# 3_3VBuck_MP2236_P1.net
KiCad netlist of a schematic drawn in EasyEDA Pro
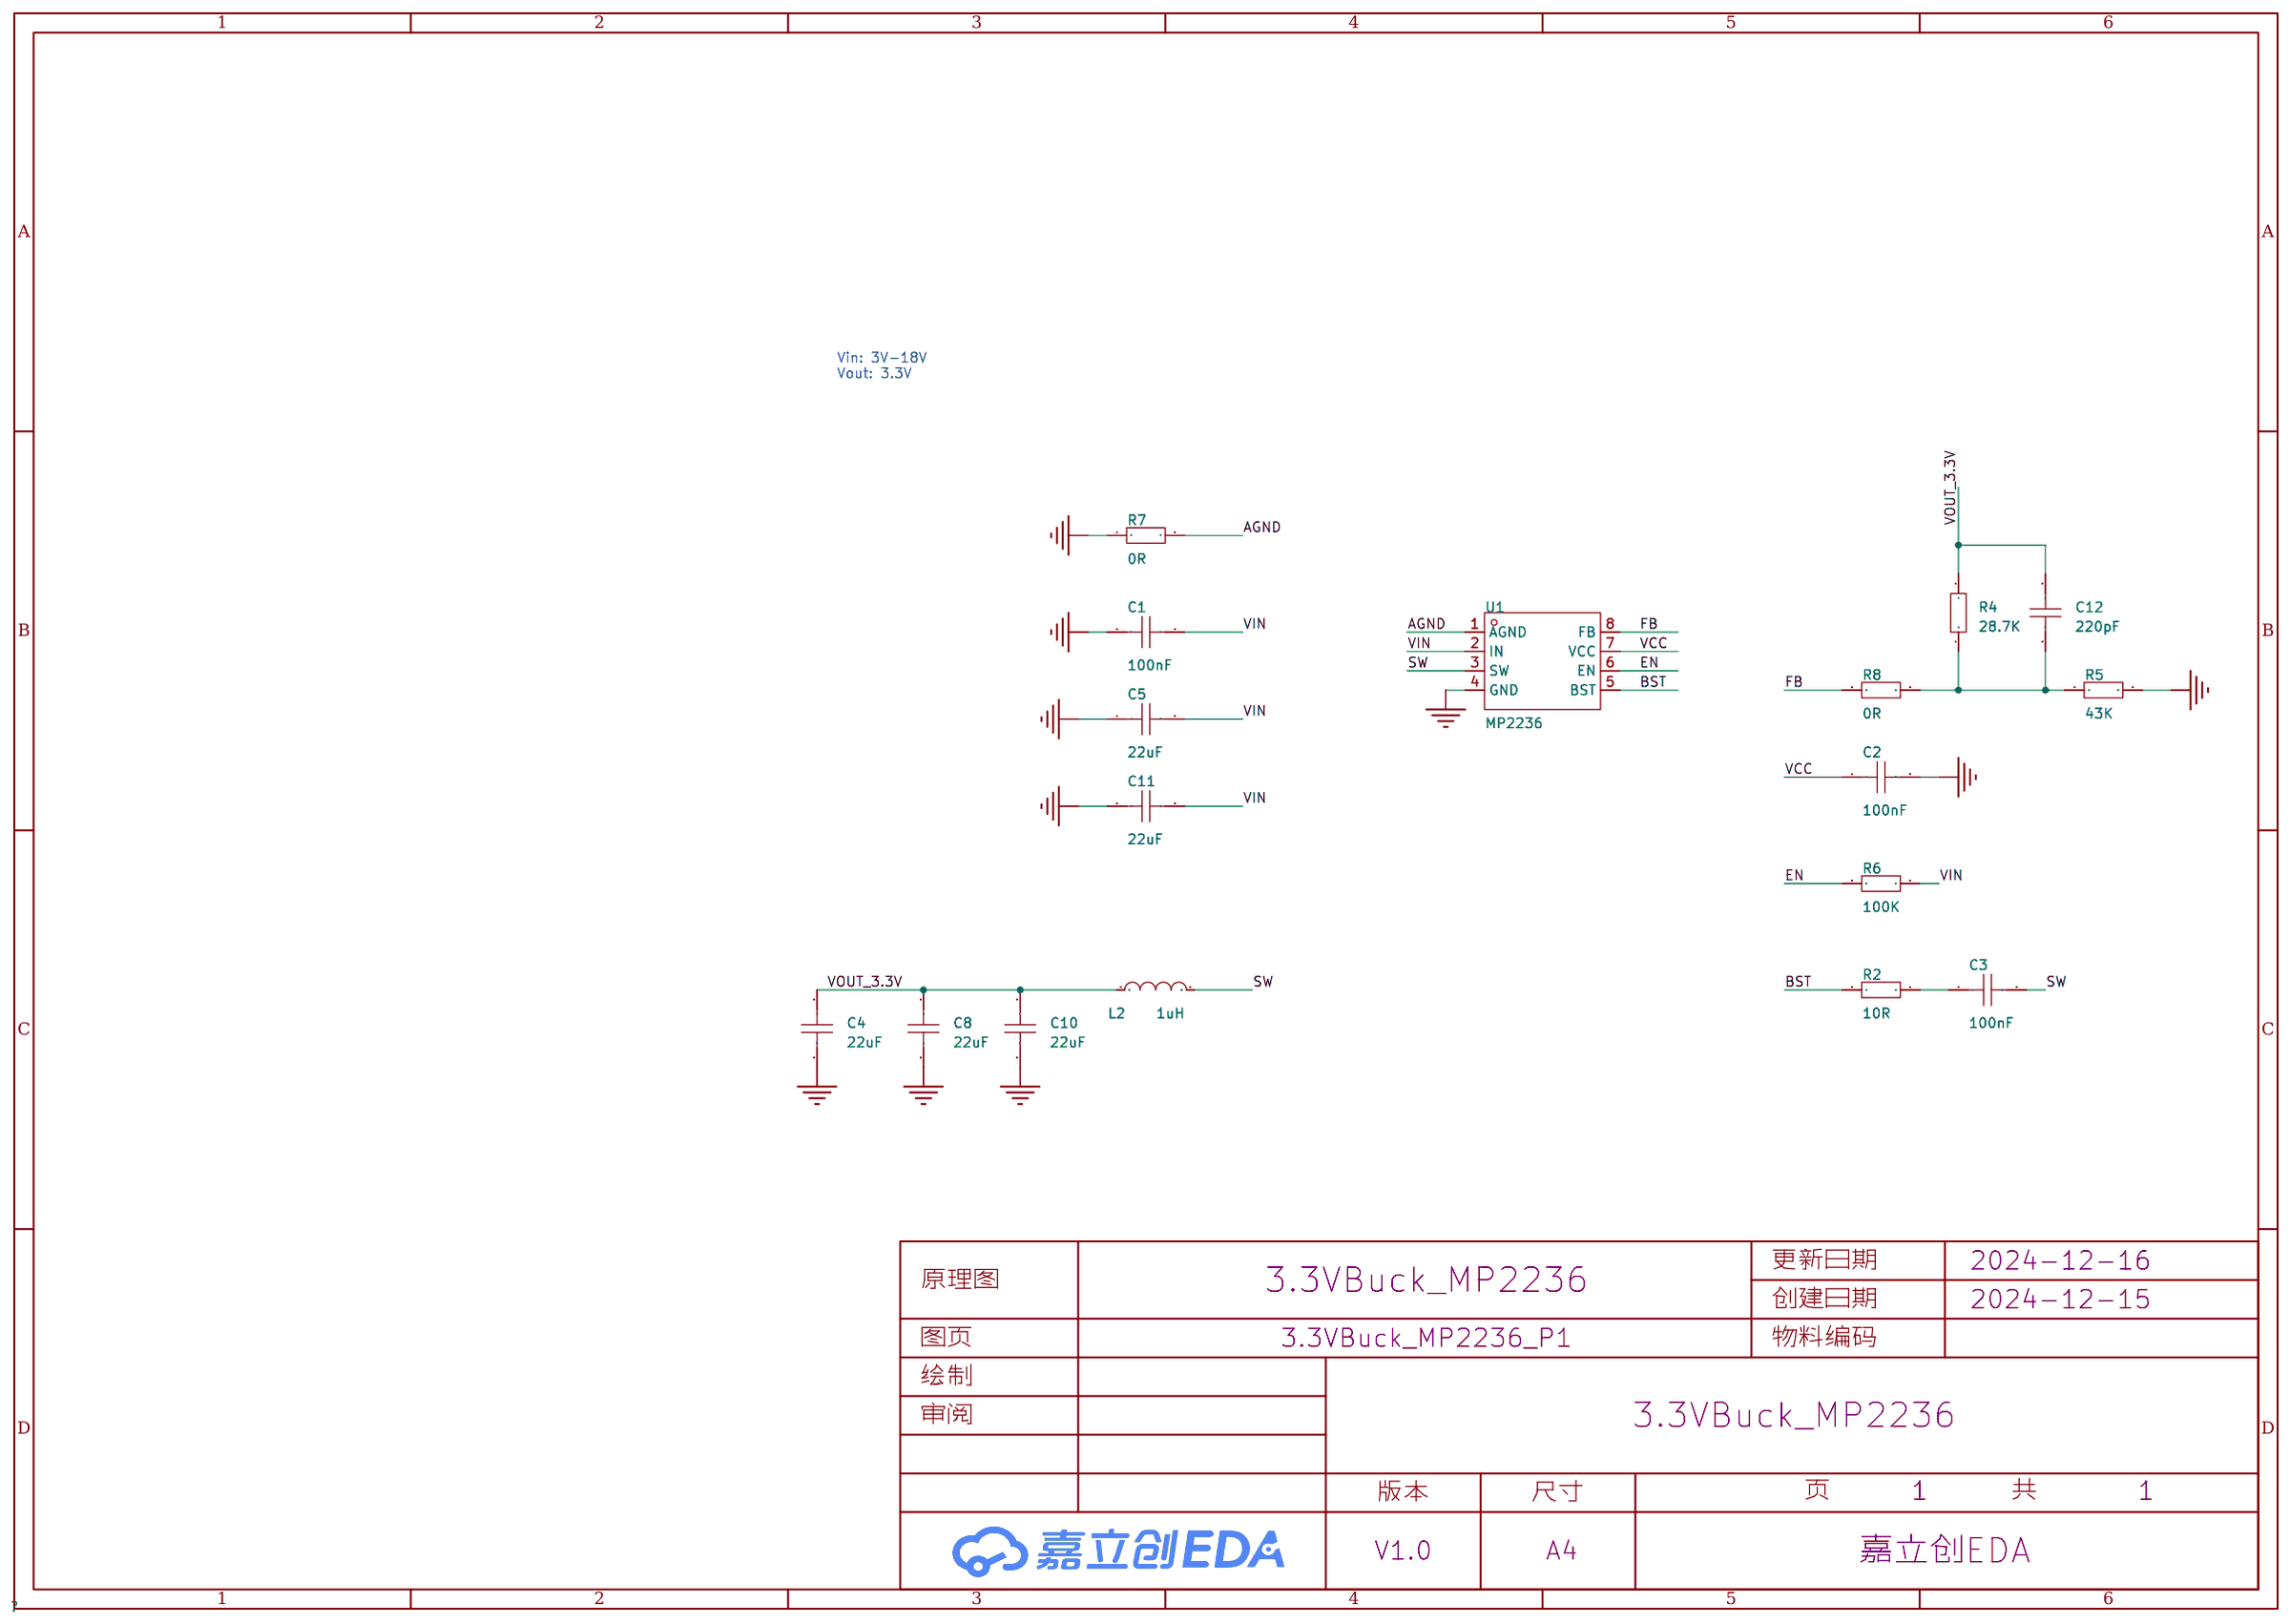
[diagram p0: schematic sheet]

(export (version "E")
  (design (tool "Eeschema 10.0.6"))
  (components
    (comp (ref "C1")
      (value "100nF")
      (footprint "easyedapro:C0805")
      (libsource (lib "easyedapro") (part "CapAcitance"))
    )
    (comp (ref "C2")
      (value "100nF")
      (footprint "easyedapro:C0805")
      (libsource (lib "easyedapro") (part "CapAcitance"))
    )
    (comp (ref "C3")
      (value "100nF")
      (footprint "easyedapro:C0805")
      (libsource (lib "easyedapro") (part "CapAcitance"))
    )
    (comp (ref "C4")
      (value "22uF")
      (footprint "easyedapro:C0805")
      (libsource (lib "easyedapro") (part "CapAcitance"))
    )
    (comp (ref "C5")
      (value "22uF")
      (footprint "easyedapro:C0805")
      (libsource (lib "easyedapro") (part "CapAcitance"))
    )
    (comp (ref "C8")
      (value "22uF")
      (footprint "easyedapro:C0805")
      (libsource (lib "easyedapro") (part "CapAcitance"))
    )
    (comp (ref "C10")
      (value "22uF")
      (footprint "easyedapro:C0805")
      (libsource (lib "easyedapro") (part "CapAcitance"))
    )
    (comp (ref "C11")
      (value "22uF")
      (footprint "easyedapro:C0805")
      (libsource (lib "easyedapro") (part "CapAcitance"))
    )
    (comp (ref "C12")
      (value "220pF")
      (footprint "easyedapro:C0805")
      (libsource (lib "easyedapro") (part "CapAcitance"))
    )
    (comp (ref "L2")
      (value "1uH")
      (footprint "easyedapro:IND-SMD_L7.1-W6.6_MJC-0603T")
      (description "电感值:5.6uH;精度:±20%;额定电流:5.5A;饱和电流(Isat):7A;类型:一体成型电感;")
      (fields
        (field (name "Manufacturer Part") "CXP0630-5R6M-AG(5.6uh)")
        (field (name "Manufacturer") "DMBJ(振宝佳)")
      )
      (libsource (lib "easyedapro") (part "CXP0630-5R6M-AG(5.6UH)"))
    )
    (comp (ref "R2") (value "10R") (footprint "easyedapro:R0805") (libsource (lib "easyedapro") (part "电阻")))
    (comp (ref "R4")
      (value "28.7K")
      (footprint "easyedapro:R0805")
      (libsource (lib "easyedapro") (part "电阻"))
    )
    (comp (ref "R5") (value "43K") (footprint "easyedapro:R0805") (libsource (lib "easyedapro") (part "电阻")))
    (comp (ref "R6") (value "100K") (footprint "easyedapro:R0805") (libsource (lib "easyedapro") (part "电阻")))
    (comp (ref "R7") (value "0R") (footprint "easyedapro:R0805") (libsource (lib "easyedapro") (part "电阻")))
    (comp (ref "R8") (value "0R") (footprint "easyedapro:R0805") (libsource (lib "easyedapro") (part "电阻")))
    (comp (ref "U1")
      (value "MP2236")
      (footprint "easyedapro:SOT-23-8_L3.0-W1.7-P0.65-LS2.8-BL")
      (libsource (lib "easyedapro") (part "MP2236"))
    )
  )
  (nets
    (net (code "1") (name "/AGND") (class "Default")
      (node (ref "R7") (pin "2") (pinfunction "2_2") (pintype "input"))
      (node (ref "U1") (pin "1") (pinfunction "AGND_1") (pintype "unspecified"))
    )
    (net (code "2") (name "/BST") (class "Default")
      (node (ref "R2") (pin "1") (pinfunction "1_1") (pintype "input"))
      (node (ref "U1") (pin "5") (pinfunction "BST_5") (pintype "unspecified"))
    )
    (net (code "3") (name "/EN") (class "Default")
      (node (ref "R6") (pin "2") (pinfunction "2_2") (pintype "input"))
      (node (ref "U1") (pin "6") (pinfunction "EN_6") (pintype "unspecified"))
    )
    (net (code "4") (name "/FB") (class "Default")
      (node (ref "R8") (pin "1") (pinfunction "1_1") (pintype "input"))
      (node (ref "U1") (pin "8") (pinfunction "FB_8") (pintype "unspecified"))
    )
    (net (code "5") (name "/SW") (class "Default")
      (node (ref "C3") (pin "2") (pinfunction "2_2") (pintype "input"))
      (node (ref "L2") (pin "2") (pinfunction "2_2") (pintype "unspecified"))
      (node (ref "U1") (pin "3") (pinfunction "SW_3") (pintype "unspecified"))
    )
    (net (code "6") (name "/VCC") (class "Default")
      (node (ref "C2") (pin "1") (pinfunction "1_1") (pintype "input"))
      (node (ref "U1") (pin "7") (pinfunction "VCC_7") (pintype "unspecified"))
    )
    (net (code "7") (name "/VIN") (class "Default")
      (node (ref "C1") (pin "2") (pinfunction "2_2") (pintype "input"))
      (node (ref "C11") (pin "2") (pinfunction "2_2") (pintype "input"))
      (node (ref "C5") (pin "2") (pinfunction "2_2") (pintype "input"))
      (node (ref "R6") (pin "1") (pinfunction "1_1") (pintype "input"))
      (node (ref "U1") (pin "2") (pinfunction "IN_2") (pintype "unspecified"))
    )
    (net (code "8") (name "/VOUT_3.3V") (class "Default")
      (node (ref "C10") (pin "1") (pinfunction "1_1") (pintype "input"))
      (node (ref "C12") (pin "2") (pinfunction "2_2") (pintype "input"))
      (node (ref "C4") (pin "1") (pinfunction "1_1") (pintype "input"))
      (node (ref "C8") (pin "1") (pinfunction "1_1") (pintype "input"))
      (node (ref "L2") (pin "1") (pinfunction "1_1") (pintype "unspecified"))
      (node (ref "R4") (pin "2") (pinfunction "2_2") (pintype "input"))
    )
    (net (code "9") (name "GND") (class "Default")
      (node (ref "C1") (pin "1") (pinfunction "1_1") (pintype "input"))
      (node (ref "C10") (pin "2") (pinfunction "2_2") (pintype "input"))
      (node (ref "C11") (pin "1") (pinfunction "1_1") (pintype "input"))
      (node (ref "C2") (pin "2") (pinfunction "2_2") (pintype "input"))
      (node (ref "C4") (pin "2") (pinfunction "2_2") (pintype "input"))
      (node (ref "C5") (pin "1") (pinfunction "1_1") (pintype "input"))
      (node (ref "C8") (pin "2") (pinfunction "2_2") (pintype "input"))
      (node (ref "R5") (pin "2") (pinfunction "2_2") (pintype "input"))
      (node (ref "R7") (pin "1") (pinfunction "1_1") (pintype "input"))
      (node (ref "U1") (pin "4") (pinfunction "GND_4") (pintype "unspecified"))
    )
    (net (code "10") (name "Net-(C3-Pad1)") (class "Default")
      (node (ref "C3") (pin "1") (pinfunction "1_1") (pintype "input"))
      (node (ref "R2") (pin "2") (pinfunction "2_2") (pintype "input"))
    )
    (net (code "11") (name "Net-(C12-Pad1)") (class "Default")
      (node (ref "C12") (pin "1") (pinfunction "1_1") (pintype "input"))
      (node (ref "R4") (pin "1") (pinfunction "1_1") (pintype "input"))
      (node (ref "R5") (pin "1") (pinfunction "1_1") (pintype "input"))
      (node (ref "R8") (pin "2") (pinfunction "2_2") (pintype "input"))
    )
  )
)
